# Hello3.net
KiCad netlist of a schematic drawn in EAGLE
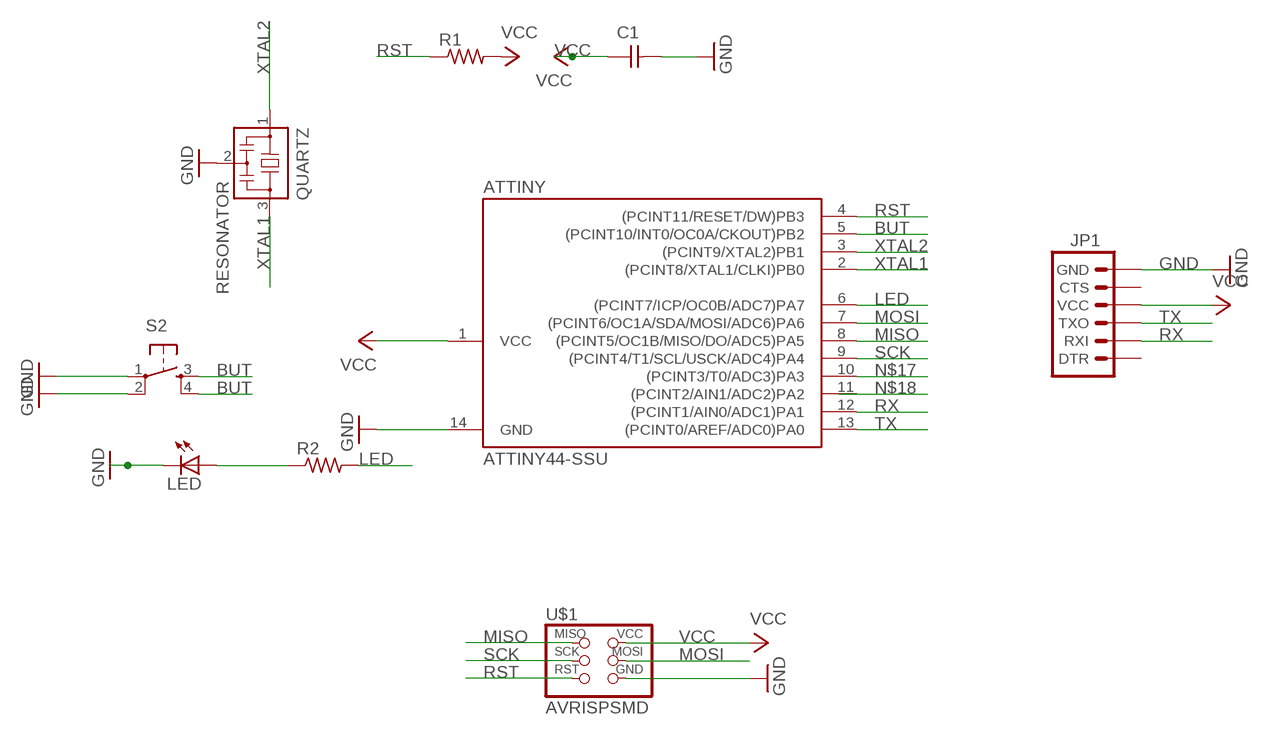
[diagram p0: schematic, sheet 1]

(export (version "E")
  (design (tool "Eeschema 10.0.6"))
  (components
    (comp (ref "ATTINY")
      (value "ATTINY44-SSU")
      (footprint "eagle-import:SOIC14")
      (libsource (lib "eagle-import") (part "ATTINY44-SSU"))
    )
    (comp (ref "C1")
      (value "UNPOLARIZED_CAPACITOR1206")
      (footprint "eagle-import:1206")
      (libsource (lib "eagle-import") (part "UNPOLARIZED_CAPACITOR1206"))
    )
    (comp (ref "JP1")
      (value "ARDUINO_SERIAL_PROGRAMLONGPADS")
      (footprint "eagle-import:1X06_LONGPADS")
      (libsource (lib "eagle-import") (part "ARDUINO_SERIAL_PROGRAMLONGPADS"))
    )
    (comp (ref "LED")
      (value "LED1206")
      (footprint "eagle-import:1206")
      (libsource (lib "eagle-import") (part "LED1206"))
    )
    (comp (ref "QUARTZ")
      (value "RESONATOR")
      (footprint "eagle-import:EFOBM")
      (libsource (lib "eagle-import") (part "RESONATOR"))
    )
    (comp (ref "R1")
      (value "RESISTOR1206")
      (footprint "eagle-import:1206")
      (libsource (lib "eagle-import") (part "RESISTOR1206"))
    )
    (comp (ref "R2")
      (value "RESISTOR1206")
      (footprint "eagle-import:1206")
      (libsource (lib "eagle-import") (part "RESISTOR1206"))
    )
    (comp (ref "S2")
      (value "6MM_SWITCH6MM_SWITCH")
      (footprint "eagle-import:6MM_SWITCH")
      (libsource (lib "eagle-import") (part "6MM_SWITCH6MM_SWITCH"))
    )
    (comp (ref "U$1")
      (value "AVRISPSMD")
      (footprint "eagle-import:2X03SMD")
      (libsource (lib "eagle-import") (part "AVRISPSMD"))
    )
  )
  (nets
    (net (code "1") (name "/BUT") (class "Default")
      (node (ref "ATTINY") (pin "5") (pinfunction "(PCINT10/INT0/OC0A/CKOUT)PB2_5") (pintype "bidirectional"))
      (node (ref "S2") (pin "3") (pinfunction "S_3") (pintype "passive"))
      (node (ref "S2") (pin "4") (pinfunction "S1_4") (pintype "passive"))
    )
    (net (code "2") (name "/LED") (class "Default")
      (node (ref "ATTINY") (pin "6") (pinfunction "(PCINT7/ICP/OC0B/ADC7)PA7_6") (pintype "bidirectional"))
      (node (ref "R2") (pin "2") (pinfunction "2_2") (pintype "passive"))
    )
    (net (code "3") (name "/MISO") (class "Default")
      (node (ref "ATTINY") (pin "8") (pinfunction "(PCINT5/OC1B/MISO/DO/ADC5)PA5_8") (pintype "bidirectional"))
      (node (ref "U$1") (pin "1") (pinfunction "MISO_1") (pintype "passive"))
    )
    (net (code "4") (name "/MOSI") (class "Default")
      (node (ref "ATTINY") (pin "7") (pinfunction "(PCINT6/OC1A/SDA/MOSI/ADC6)PA6_7") (pintype "bidirectional"))
      (node (ref "U$1") (pin "4") (pinfunction "MOSI_4") (pintype "passive"))
    )
    (net (code "5") (name "/N$17") (class "Default")
      (node (ref "ATTINY") (pin "10") (pinfunction "(PCINT3/T0/ADC3)PA3_10") (pintype "bidirectional"))
    )
    (net (code "7") (name "/RST") (class "Default")
      (node (ref "ATTINY") (pin "4") (pinfunction "(PCINT11/RESET/DW)PB3_4") (pintype "bidirectional"))
      (node (ref "R1") (pin "1") (pinfunction "1_1") (pintype "passive"))
      (node (ref "U$1") (pin "5") (pinfunction "RST_5") (pintype "passive"))
    )
    (net (code "8") (name "/RX") (class "Default")
      (node (ref "ATTINY") (pin "12") (pinfunction "(PCINT1/AIN0/ADC1)PA1_12") (pintype "bidirectional"))
      (node (ref "JP1") (pin "2") (pinfunction "RXI_2") (pintype "passive"))
    )
    (net (code "9") (name "/SCK") (class "Default")
      (node (ref "ATTINY") (pin "9") (pinfunction "(PCINT4/T1/SCL/USCK/ADC4)PA4_9") (pintype "bidirectional"))
      (node (ref "U$1") (pin "3") (pinfunction "SCK_3") (pintype "passive"))
    )
    (net (code "10") (name "/TX") (class "Default")
      (node (ref "ATTINY") (pin "13") (pinfunction "(PCINT0/AREF/ADC0)PA0_13") (pintype "bidirectional"))
      (node (ref "JP1") (pin "3") (pinfunction "TXO_3") (pintype "passive"))
    )
    (net (code "11") (name "/XTAL1") (class "Default")
      (node (ref "ATTINY") (pin "2") (pinfunction "(PCINT8/XTAL1/CLKI)PB0_2") (pintype "bidirectional"))
      (node (ref "QUARTZ") (pin "3") (pinfunction "3_3") (pintype "passive"))
    )
    (net (code "12") (name "/XTAL2") (class "Default")
      (node (ref "ATTINY") (pin "3") (pinfunction "(PCINT9/XTAL2)PB1_3") (pintype "bidirectional"))
      (node (ref "QUARTZ") (pin "1") (pinfunction "1_1") (pintype "passive"))
    )
    (net (code "13") (name "GND") (class "Default")
      (node (ref "ATTINY") (pin "14") (pinfunction "GND_14") (pintype "power_in"))
      (node (ref "C1") (pin "2") (pinfunction "2_2") (pintype "passive"))
      (node (ref "JP1") (pin "6") (pinfunction "GND_6") (pintype "passive"))
      (node (ref "LED") (pin "2") (pinfunction "C_2") (pintype "passive"))
      (node (ref "QUARTZ") (pin "2") (pinfunction "2_2") (pintype "passive"))
      (node (ref "S2") (pin "1") (pinfunction "P_1") (pintype "passive"))
      (node (ref "S2") (pin "2") (pinfunction "P1_2") (pintype "passive"))
      (node (ref "U$1") (pin "6") (pinfunction "GND_6") (pintype "passive"))
    )
    (net (code "14") (name "Net-(LED-A)") (class "Default")
      (node (ref "LED") (pin "1") (pinfunction "A_1") (pintype "passive"))
      (node (ref "R2") (pin "1") (pinfunction "1_1") (pintype "passive"))
    )
    (net (code "15") (name "VCC") (class "Default")
      (node (ref "ATTINY") (pin "1") (pinfunction "VCC_1") (pintype "power_in"))
      (node (ref "C1") (pin "1") (pinfunction "1_1") (pintype "passive"))
      (node (ref "JP1") (pin "4") (pinfunction "VCC_4") (pintype "passive"))
      (node (ref "R1") (pin "2") (pinfunction "2_2") (pintype "passive"))
      (node (ref "U$1") (pin "2") (pinfunction "VCC_2") (pintype "passive"))
    )
    (net (code "16") (name "unconnected-(ATTINY-(PCINT2{slash}AIN1{slash}ADC2)PA2-Pad11)") (class "Default")
      (node (ref "ATTINY") (pin "11") (pinfunction "(PCINT2/AIN1/ADC2)PA2_11") (pintype "bidirectional"))
    )
    (net (code "17") (name "unconnected-(JP1-CTS-Pad5)") (class "Default")
      (node (ref "JP1") (pin "5") (pinfunction "CTS_5") (pintype "passive"))
    )
    (net (code "18") (name "unconnected-(JP1-DTR-Pad1)") (class "Default")
      (node (ref "JP1") (pin "1") (pinfunction "DTR_1") (pintype "passive"))
    )
  )
)
